# MrMIDI_L2.net
KiCad netlist of a schematic drawn in EAGLE
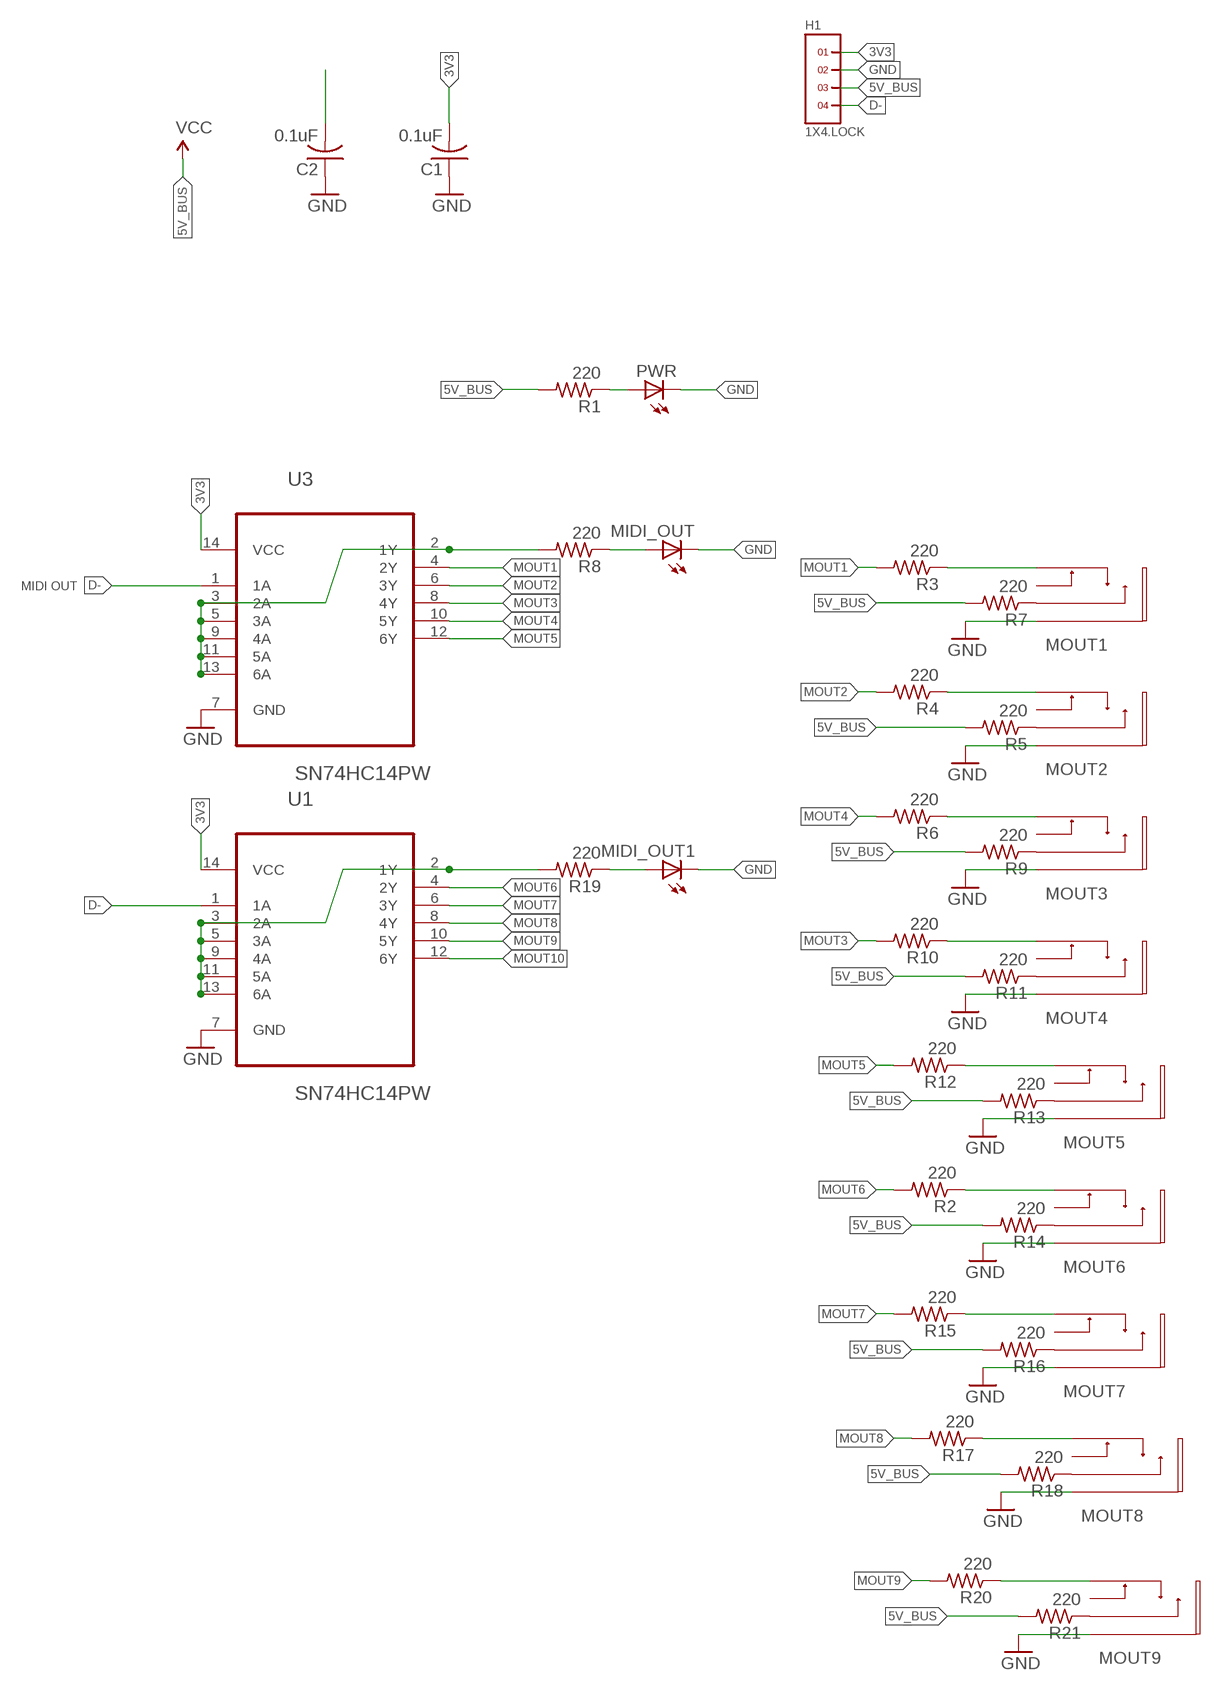
[diagram p0: schematic, sheet 1]

(export (version "E")
  (design (tool "Eeschema 10.0.6"))
  (components
    (comp (ref "C1")
      (value "0.1uF")
      (footprint "eagle-import:RCL_C0603K")
      (libsource (lib "eagle-import") (part "RCL_C-USC0603K"))
    )
    (comp (ref "C2")
      (value "0.1uF")
      (footprint "eagle-import:RCL_C0603K")
      (libsource (lib "eagle-import") (part "RCL_C-USC0603K"))
    )
    (comp (ref "H1")
      (value "1X4.LOCK")
      (footprint "eagle-import:1X4.LOCK")
      (libsource (lib "eagle-import") (part "1X4.LOCK"))
    )
    (comp (ref "MIDI_OUT")
      (value "LEDCHIPLED_0603")
      (footprint "eagle-import:CHIPLED_0603")
      (libsource (lib "eagle-import") (part "LEDCHIPLED_0603"))
    )
    (comp (ref "MIDI_OUT1")
      (value "LEDCHIPLED_0603")
      (footprint "eagle-import:CHIPLED_0603")
      (libsource (lib "eagle-import") (part "LEDCHIPLED_0603"))
    )
    (comp (ref "MOUT1")
      (value "PJ327E")
      (footprint "eagle-import:PJ327")
      (libsource (lib "eagle-import") (part "PJ327E"))
    )
    (comp (ref "MOUT2")
      (value "PJ327E")
      (footprint "eagle-import:PJ327")
      (libsource (lib "eagle-import") (part "PJ327E"))
    )
    (comp (ref "MOUT3")
      (value "PJ327E")
      (footprint "eagle-import:PJ327")
      (libsource (lib "eagle-import") (part "PJ327E"))
    )
    (comp (ref "MOUT4")
      (value "PJ327E")
      (footprint "eagle-import:PJ327")
      (libsource (lib "eagle-import") (part "PJ327E"))
    )
    (comp (ref "MOUT5")
      (value "PJ327E")
      (footprint "eagle-import:PJ327")
      (libsource (lib "eagle-import") (part "PJ327E"))
    )
    (comp (ref "MOUT6")
      (value "PJ327E")
      (footprint "eagle-import:PJ327")
      (libsource (lib "eagle-import") (part "PJ327E"))
    )
    (comp (ref "MOUT7")
      (value "PJ327E")
      (footprint "eagle-import:PJ327")
      (libsource (lib "eagle-import") (part "PJ327E"))
    )
    (comp (ref "MOUT8")
      (value "PJ327E")
      (footprint "eagle-import:PJ327")
      (libsource (lib "eagle-import") (part "PJ327E"))
    )
    (comp (ref "MOUT9")
      (value "PJ327E")
      (footprint "eagle-import:PJ327")
      (libsource (lib "eagle-import") (part "PJ327E"))
    )
    (comp (ref "PWR")
      (value "LEDCHIPLED_0603")
      (footprint "eagle-import:CHIPLED_0603")
      (libsource (lib "eagle-import") (part "LEDCHIPLED_0603"))
    )
    (comp (ref "R1")
      (value "220")
      (footprint "eagle-import:RCL_R0402")
      (libsource (lib "eagle-import") (part "RCL_R-US_R0402"))
    )
    (comp (ref "R2")
      (value "220")
      (footprint "eagle-import:RCL_R0402")
      (libsource (lib "eagle-import") (part "RCL_R-US_R0402"))
    )
    (comp (ref "R3")
      (value "220")
      (footprint "eagle-import:RCL_R0402")
      (libsource (lib "eagle-import") (part "RCL_R-US_R0402"))
    )
    (comp (ref "R4")
      (value "220")
      (footprint "eagle-import:RCL_R0402")
      (libsource (lib "eagle-import") (part "RCL_R-US_R0402"))
    )
    (comp (ref "R5")
      (value "220")
      (footprint "eagle-import:RCL_R0402")
      (libsource (lib "eagle-import") (part "RCL_R-US_R0402"))
    )
    (comp (ref "R6")
      (value "220")
      (footprint "eagle-import:RCL_R0402")
      (libsource (lib "eagle-import") (part "RCL_R-US_R0402"))
    )
    (comp (ref "R7")
      (value "220")
      (footprint "eagle-import:RCL_R0402")
      (libsource (lib "eagle-import") (part "RCL_R-US_R0402"))
    )
    (comp (ref "R8")
      (value "220")
      (footprint "eagle-import:RCL_R0402")
      (libsource (lib "eagle-import") (part "RCL_R-US_R0402"))
    )
    (comp (ref "R9")
      (value "220")
      (footprint "eagle-import:RCL_R0402")
      (libsource (lib "eagle-import") (part "RCL_R-US_R0402"))
    )
    (comp (ref "R10")
      (value "220")
      (footprint "eagle-import:RCL_R0402")
      (libsource (lib "eagle-import") (part "RCL_R-US_R0402"))
    )
    (comp (ref "R11")
      (value "220")
      (footprint "eagle-import:RCL_R0402")
      (libsource (lib "eagle-import") (part "RCL_R-US_R0402"))
    )
    (comp (ref "R12")
      (value "220")
      (footprint "eagle-import:RCL_R0402")
      (libsource (lib "eagle-import") (part "RCL_R-US_R0402"))
    )
    (comp (ref "R13")
      (value "220")
      (footprint "eagle-import:RCL_R0402")
      (libsource (lib "eagle-import") (part "RCL_R-US_R0402"))
    )
    (comp (ref "R14")
      (value "220")
      (footprint "eagle-import:RCL_R0402")
      (libsource (lib "eagle-import") (part "RCL_R-US_R0402"))
    )
    (comp (ref "R15")
      (value "220")
      (footprint "eagle-import:RCL_R0402")
      (libsource (lib "eagle-import") (part "RCL_R-US_R0402"))
    )
    (comp (ref "R16")
      (value "220")
      (footprint "eagle-import:RCL_R0402")
      (libsource (lib "eagle-import") (part "RCL_R-US_R0402"))
    )
    (comp (ref "R17")
      (value "220")
      (footprint "eagle-import:RCL_R0402")
      (libsource (lib "eagle-import") (part "RCL_R-US_R0402"))
    )
    (comp (ref "R18")
      (value "220")
      (footprint "eagle-import:RCL_R0402")
      (libsource (lib "eagle-import") (part "RCL_R-US_R0402"))
    )
    (comp (ref "R19")
      (value "220")
      (footprint "eagle-import:RCL_R0402")
      (libsource (lib "eagle-import") (part "RCL_R-US_R0402"))
    )
    (comp (ref "R20")
      (value "220")
      (footprint "eagle-import:RCL_R0402")
      (libsource (lib "eagle-import") (part "RCL_R-US_R0402"))
    )
    (comp (ref "R21")
      (value "220")
      (footprint "eagle-import:RCL_R0402")
      (libsource (lib "eagle-import") (part "RCL_R-US_R0402"))
    )
    (comp (ref "U1")
      (value "SN74HC14PW")
      (footprint "eagle-import:SOP65P640X120-14N")
      (libsource (lib "eagle-import") (part "SN74HC14PW"))
    )
    (comp (ref "U3")
      (value "SN74HC14PW")
      (footprint "eagle-import:SOP65P640X120-14N")
      (libsource (lib "eagle-import") (part "SN74HC14PW"))
    )
  )
  (nets
    (net (code "1") (name "3V3") (class "Default")
      (node (ref "C1") (pin "2") (pinfunction "2_2") (pintype "passive"))
      (node (ref "H1") (pin "1") (pinfunction "1_1") (pintype "bidirectional"))
      (node (ref "U1") (pin "14") (pinfunction "VCC_14") (pintype "power_in"))
      (node (ref "U3") (pin "14") (pinfunction "VCC_14") (pintype "power_in"))
    )
    (net (code "2") (name "5V_BUS") (class "Default")
      (node (ref "C2") (pin "2") (pinfunction "2_2") (pintype "passive"))
      (node (ref "H1") (pin "3") (pinfunction "3_3") (pintype "bidirectional"))
      (node (ref "R1") (pin "2") (pinfunction "2_2") (pintype "passive"))
      (node (ref "R11") (pin "2") (pinfunction "2_2") (pintype "passive"))
      (node (ref "R13") (pin "2") (pinfunction "2_2") (pintype "passive"))
      (node (ref "R14") (pin "2") (pinfunction "2_2") (pintype "passive"))
      (node (ref "R16") (pin "2") (pinfunction "2_2") (pintype "passive"))
      (node (ref "R18") (pin "2") (pinfunction "2_2") (pintype "passive"))
      (node (ref "R21") (pin "2") (pinfunction "2_2") (pintype "passive"))
      (node (ref "R5") (pin "2") (pinfunction "2_2") (pintype "passive"))
      (node (ref "R7") (pin "2") (pinfunction "2_2") (pintype "passive"))
      (node (ref "R9") (pin "2") (pinfunction "2_2") (pintype "passive"))
    )
    (net (code "3") (name "D-") (class "Default")
      (node (ref "H1") (pin "4") (pinfunction "4_4") (pintype "bidirectional"))
      (node (ref "U1") (pin "1") (pinfunction "1A_1") (pintype "input"))
      (node (ref "U3") (pin "1") (pinfunction "1A_1") (pintype "input"))
    )
    (net (code "4") (name "GND") (class "Default")
      (node (ref "C1") (pin "1") (pinfunction "1_1") (pintype "passive"))
      (node (ref "C2") (pin "1") (pinfunction "1_1") (pintype "passive"))
      (node (ref "H1") (pin "2") (pinfunction "2_2") (pintype "bidirectional"))
      (node (ref "MIDI_OUT") (pin "C") (pinfunction "C_C") (pintype "passive"))
      (node (ref "MIDI_OUT1") (pin "C") (pinfunction "C_C") (pintype "passive"))
      (node (ref "MOUT1") (pin "P$1") (pinfunction "P$1_P$1") (pintype "bidirectional"))
      (node (ref "MOUT1") (pin "P$4") (pinfunction "P$1_P$4") (pintype "bidirectional"))
      (node (ref "MOUT2") (pin "P$1") (pinfunction "P$1_P$1") (pintype "bidirectional"))
      (node (ref "MOUT2") (pin "P$4") (pinfunction "P$1_P$4") (pintype "bidirectional"))
      (node (ref "MOUT3") (pin "P$1") (pinfunction "P$1_P$1") (pintype "bidirectional"))
      (node (ref "MOUT3") (pin "P$4") (pinfunction "P$1_P$4") (pintype "bidirectional"))
      (node (ref "MOUT4") (pin "P$1") (pinfunction "P$1_P$1") (pintype "bidirectional"))
      (node (ref "MOUT4") (pin "P$4") (pinfunction "P$1_P$4") (pintype "bidirectional"))
      (node (ref "MOUT5") (pin "P$1") (pinfunction "P$1_P$1") (pintype "bidirectional"))
      (node (ref "MOUT5") (pin "P$4") (pinfunction "P$1_P$4") (pintype "bidirectional"))
      (node (ref "MOUT6") (pin "P$1") (pinfunction "P$1_P$1") (pintype "bidirectional"))
      (node (ref "MOUT6") (pin "P$4") (pinfunction "P$1_P$4") (pintype "bidirectional"))
      (node (ref "MOUT7") (pin "P$1") (pinfunction "P$1_P$1") (pintype "bidirectional"))
      (node (ref "MOUT7") (pin "P$4") (pinfunction "P$1_P$4") (pintype "bidirectional"))
      (node (ref "MOUT8") (pin "P$1") (pinfunction "P$1_P$1") (pintype "bidirectional"))
      (node (ref "MOUT8") (pin "P$4") (pinfunction "P$1_P$4") (pintype "bidirectional"))
      (node (ref "MOUT9") (pin "P$1") (pinfunction "P$1_P$1") (pintype "bidirectional"))
      (node (ref "MOUT9") (pin "P$4") (pinfunction "P$1_P$4") (pintype "bidirectional"))
      (node (ref "PWR") (pin "C") (pinfunction "C_C") (pintype "passive"))
      (node (ref "U1") (pin "7") (pinfunction "GND_7") (pintype "passive"))
      (node (ref "U3") (pin "7") (pinfunction "GND_7") (pintype "passive"))
    )
    (net (code "5") (name "MOUT1") (class "Default")
      (node (ref "R3") (pin "2") (pinfunction "2_2") (pintype "passive"))
      (node (ref "U3") (pin "4") (pinfunction "2Y_4") (pintype "output"))
    )
    (net (code "6") (name "MOUT2") (class "Default")
      (node (ref "R4") (pin "2") (pinfunction "2_2") (pintype "passive"))
      (node (ref "U3") (pin "6") (pinfunction "3Y_6") (pintype "output"))
    )
    (net (code "7") (name "MOUT3") (class "Default")
      (node (ref "R10") (pin "2") (pinfunction "2_2") (pintype "passive"))
      (node (ref "U3") (pin "8") (pinfunction "4Y_8") (pintype "output"))
    )
    (net (code "8") (name "MOUT4") (class "Default")
      (node (ref "R6") (pin "2") (pinfunction "2_2") (pintype "passive"))
      (node (ref "U3") (pin "10") (pinfunction "5Y_10") (pintype "output"))
    )
    (net (code "9") (name "MOUT5") (class "Default")
      (node (ref "R12") (pin "2") (pinfunction "2_2") (pintype "passive"))
      (node (ref "U3") (pin "12") (pinfunction "6Y_12") (pintype "output"))
    )
    (net (code "10") (name "MOUT6") (class "Default")
      (node (ref "R2") (pin "2") (pinfunction "2_2") (pintype "passive"))
      (node (ref "U1") (pin "4") (pinfunction "2Y_4") (pintype "output"))
    )
    (net (code "11") (name "MOUT7") (class "Default")
      (node (ref "R15") (pin "2") (pinfunction "2_2") (pintype "passive"))
      (node (ref "U1") (pin "6") (pinfunction "3Y_6") (pintype "output"))
    )
    (net (code "12") (name "MOUT8") (class "Default")
      (node (ref "R17") (pin "2") (pinfunction "2_2") (pintype "passive"))
      (node (ref "U1") (pin "8") (pinfunction "4Y_8") (pintype "output"))
    )
    (net (code "13") (name "MOUT9") (class "Default")
      (node (ref "R20") (pin "2") (pinfunction "2_2") (pintype "passive"))
      (node (ref "U1") (pin "10") (pinfunction "5Y_10") (pintype "output"))
    )
    (net (code "14") (name "MOUT10") (class "Default")
      (node (ref "U1") (pin "12") (pinfunction "6Y_12") (pintype "output"))
    )
    (net (code "15") (name "Net-(MIDI_OUT-PadA)") (class "Default")
      (node (ref "MIDI_OUT") (pin "A") (pinfunction "A_A") (pintype "passive"))
      (node (ref "R8") (pin "1") (pinfunction "1_1") (pintype "passive"))
    )
    (net (code "16") (name "Net-(MIDI_OUT1-PadA)") (class "Default")
      (node (ref "MIDI_OUT1") (pin "A") (pinfunction "A_A") (pintype "passive"))
      (node (ref "R19") (pin "1") (pinfunction "1_1") (pintype "passive"))
    )
    (net (code "17") (name "Net-(MOUT1-PadP$2)") (class "Default")
      (node (ref "MOUT1") (pin "P$2") (pinfunction "P$2_P$2") (pintype "bidirectional"))
      (node (ref "R3") (pin "1") (pinfunction "1_1") (pintype "passive"))
    )
    (net (code "18") (name "Net-(MOUT1-PadP$3)") (class "Default")
      (node (ref "MOUT1") (pin "P$3") (pinfunction "P$3_P$3") (pintype "bidirectional"))
      (node (ref "R7") (pin "1") (pinfunction "1_1") (pintype "passive"))
    )
    (net (code "19") (name "Net-(MOUT2-PadP$2)") (class "Default")
      (node (ref "MOUT2") (pin "P$2") (pinfunction "P$2_P$2") (pintype "bidirectional"))
      (node (ref "R4") (pin "1") (pinfunction "1_1") (pintype "passive"))
    )
    (net (code "20") (name "Net-(MOUT2-PadP$3)") (class "Default")
      (node (ref "MOUT2") (pin "P$3") (pinfunction "P$3_P$3") (pintype "bidirectional"))
      (node (ref "R5") (pin "1") (pinfunction "1_1") (pintype "passive"))
    )
    (net (code "21") (name "Net-(MOUT3-PadP$2)") (class "Default")
      (node (ref "MOUT3") (pin "P$2") (pinfunction "P$2_P$2") (pintype "bidirectional"))
      (node (ref "R6") (pin "1") (pinfunction "1_1") (pintype "passive"))
    )
    (net (code "22") (name "Net-(MOUT3-PadP$3)") (class "Default")
      (node (ref "MOUT3") (pin "P$3") (pinfunction "P$3_P$3") (pintype "bidirectional"))
      (node (ref "R9") (pin "1") (pinfunction "1_1") (pintype "passive"))
    )
    (net (code "23") (name "Net-(MOUT4-PadP$2)") (class "Default")
      (node (ref "MOUT4") (pin "P$2") (pinfunction "P$2_P$2") (pintype "bidirectional"))
      (node (ref "R10") (pin "1") (pinfunction "1_1") (pintype "passive"))
    )
    (net (code "24") (name "Net-(MOUT4-PadP$3)") (class "Default")
      (node (ref "MOUT4") (pin "P$3") (pinfunction "P$3_P$3") (pintype "bidirectional"))
      (node (ref "R11") (pin "1") (pinfunction "1_1") (pintype "passive"))
    )
    (net (code "25") (name "Net-(MOUT5-PadP$2)") (class "Default")
      (node (ref "MOUT5") (pin "P$2") (pinfunction "P$2_P$2") (pintype "bidirectional"))
      (node (ref "R12") (pin "1") (pinfunction "1_1") (pintype "passive"))
    )
    (net (code "26") (name "Net-(MOUT5-PadP$3)") (class "Default")
      (node (ref "MOUT5") (pin "P$3") (pinfunction "P$3_P$3") (pintype "bidirectional"))
      (node (ref "R13") (pin "1") (pinfunction "1_1") (pintype "passive"))
    )
    (net (code "27") (name "Net-(MOUT6-PadP$2)") (class "Default")
      (node (ref "MOUT6") (pin "P$2") (pinfunction "P$2_P$2") (pintype "bidirectional"))
      (node (ref "R2") (pin "1") (pinfunction "1_1") (pintype "passive"))
    )
    (net (code "28") (name "Net-(MOUT6-PadP$3)") (class "Default")
      (node (ref "MOUT6") (pin "P$3") (pinfunction "P$3_P$3") (pintype "bidirectional"))
      (node (ref "R14") (pin "1") (pinfunction "1_1") (pintype "passive"))
    )
    (net (code "29") (name "Net-(MOUT7-PadP$2)") (class "Default")
      (node (ref "MOUT7") (pin "P$2") (pinfunction "P$2_P$2") (pintype "bidirectional"))
      (node (ref "R15") (pin "1") (pinfunction "1_1") (pintype "passive"))
    )
    (net (code "30") (name "Net-(MOUT7-PadP$3)") (class "Default")
      (node (ref "MOUT7") (pin "P$3") (pinfunction "P$3_P$3") (pintype "bidirectional"))
      (node (ref "R16") (pin "1") (pinfunction "1_1") (pintype "passive"))
    )
    (net (code "31") (name "Net-(MOUT8-PadP$2)") (class "Default")
      (node (ref "MOUT8") (pin "P$2") (pinfunction "P$2_P$2") (pintype "bidirectional"))
      (node (ref "R17") (pin "1") (pinfunction "1_1") (pintype "passive"))
    )
    (net (code "32") (name "Net-(MOUT8-PadP$3)") (class "Default")
      (node (ref "MOUT8") (pin "P$3") (pinfunction "P$3_P$3") (pintype "bidirectional"))
      (node (ref "R18") (pin "1") (pinfunction "1_1") (pintype "passive"))
    )
    (net (code "33") (name "Net-(MOUT9-PadP$2)") (class "Default")
      (node (ref "MOUT9") (pin "P$2") (pinfunction "P$2_P$2") (pintype "bidirectional"))
      (node (ref "R20") (pin "1") (pinfunction "1_1") (pintype "passive"))
    )
    (net (code "34") (name "Net-(MOUT9-PadP$3)") (class "Default")
      (node (ref "MOUT9") (pin "P$3") (pinfunction "P$3_P$3") (pintype "bidirectional"))
      (node (ref "R21") (pin "1") (pinfunction "1_1") (pintype "passive"))
    )
    (net (code "35") (name "Net-(PWR-PadA)") (class "Default")
      (node (ref "PWR") (pin "A") (pinfunction "A_A") (pintype "passive"))
      (node (ref "R1") (pin "1") (pinfunction "1_1") (pintype "passive"))
    )
    (net (code "36") (name "Net-(U1-1Y)") (class "Default")
      (node (ref "R19") (pin "2") (pinfunction "2_2") (pintype "passive"))
      (node (ref "U1") (pin "11") (pinfunction "5A_11") (pintype "input"))
      (node (ref "U1") (pin "13") (pinfunction "6A_13") (pintype "input"))
      (node (ref "U1") (pin "2") (pinfunction "1Y_2") (pintype "output"))
      (node (ref "U1") (pin "3") (pinfunction "2A_3") (pintype "input"))
      (node (ref "U1") (pin "5") (pinfunction "3A_5") (pintype "input"))
      (node (ref "U1") (pin "9") (pinfunction "4A_9") (pintype "input"))
    )
    (net (code "37") (name "Net-(U3-1Y)") (class "Default")
      (node (ref "R8") (pin "2") (pinfunction "2_2") (pintype "passive"))
      (node (ref "U3") (pin "11") (pinfunction "5A_11") (pintype "input"))
      (node (ref "U3") (pin "13") (pinfunction "6A_13") (pintype "input"))
      (node (ref "U3") (pin "2") (pinfunction "1Y_2") (pintype "output"))
      (node (ref "U3") (pin "3") (pinfunction "2A_3") (pintype "input"))
      (node (ref "U3") (pin "5") (pinfunction "3A_5") (pintype "input"))
      (node (ref "U3") (pin "9") (pinfunction "4A_9") (pintype "input"))
    )
    (net (code "38") (name "unconnected-(MOUT1-PadP$5)") (class "Default")
      (node (ref "MOUT1") (pin "P$5") (pinfunction "P$5_P$5") (pintype "bidirectional"))
    )
    (net (code "39") (name "unconnected-(MOUT2-PadP$5)") (class "Default")
      (node (ref "MOUT2") (pin "P$5") (pinfunction "P$5_P$5") (pintype "bidirectional"))
    )
    (net (code "40") (name "unconnected-(MOUT3-PadP$5)") (class "Default")
      (node (ref "MOUT3") (pin "P$5") (pinfunction "P$5_P$5") (pintype "bidirectional"))
    )
    (net (code "41") (name "unconnected-(MOUT4-PadP$5)") (class "Default")
      (node (ref "MOUT4") (pin "P$5") (pinfunction "P$5_P$5") (pintype "bidirectional"))
    )
    (net (code "42") (name "unconnected-(MOUT5-PadP$5)") (class "Default")
      (node (ref "MOUT5") (pin "P$5") (pinfunction "P$5_P$5") (pintype "bidirectional"))
    )
    (net (code "43") (name "unconnected-(MOUT6-PadP$5)") (class "Default")
      (node (ref "MOUT6") (pin "P$5") (pinfunction "P$5_P$5") (pintype "bidirectional"))
    )
    (net (code "44") (name "unconnected-(MOUT7-PadP$5)") (class "Default")
      (node (ref "MOUT7") (pin "P$5") (pinfunction "P$5_P$5") (pintype "bidirectional"))
    )
    (net (code "45") (name "unconnected-(MOUT8-PadP$5)") (class "Default")
      (node (ref "MOUT8") (pin "P$5") (pinfunction "P$5_P$5") (pintype "bidirectional"))
    )
    (net (code "46") (name "unconnected-(MOUT9-PadP$5)") (class "Default")
      (node (ref "MOUT9") (pin "P$5") (pinfunction "P$5_P$5") (pintype "bidirectional"))
    )
  )
)
